# Power_Supply.net
KiCad netlist of a schematic drawn in Altium Designer
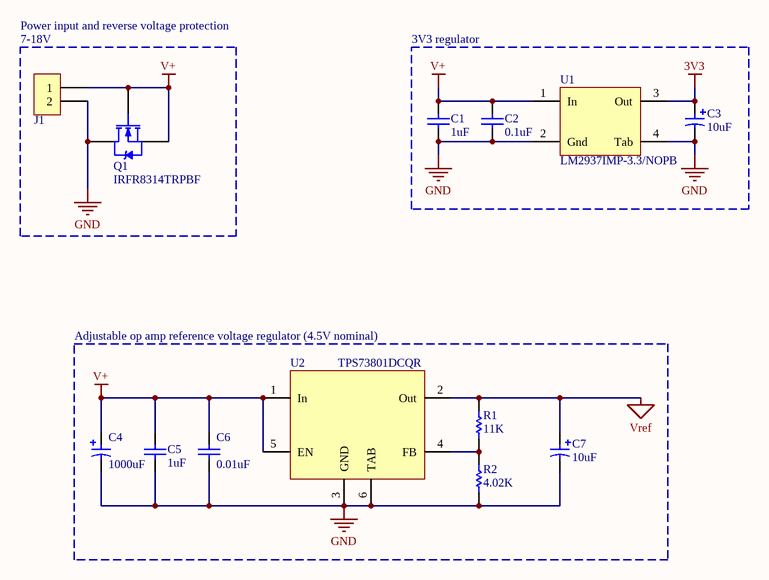
[diagram p0: Power_Supply.SchDoc]

(export (version "E")
  (design (tool "Eeschema 10.0.6"))
  (components
    (comp (ref "C1")
      (value "1uF")
      (footprint "CAPC1608X09N")
      (fields
        (field (name "DIGIKEY PART NUMBER") "490-10487-1-ND")
        (field (name "VOLTAGE") "35V")
        (field (name "MANUFACTURER") "Murata")
      )
      (libsource (lib "Speaker Library") (part "CAP CER 1uF 0603"))
    )
    (comp (ref "C2")
      (value "0.1uF")
      (footprint "CAPC1608X09N")
      (fields
        (field (name "DIGIKEY PART NUMBER") "490-1519-1-ND")
        (field (name "VOLTAGE") "50V")
        (field (name "TOLERANCE") "10%")
      )
      (libsource (lib "Speaker Library") (part "CAP CER 0.1uF 0603"))
    )
    (comp (ref "C3")
      (value "10uF")
      (footprint "CAPMP3216X18N")
      (fields
        (field (name "DIGIKEY PART NUMBER") "399-8431-1-ND")
        (field (name "VOLTAGE") "10V")
        (field (name "TOLERANCE") "10%")
      )
      (libsource (lib "Speaker Library") (part "CAP TANT 10uF 1.8 OHM 10V 1206"))
    )
    (comp (ref "C4")
      (value "1000uF")
      (footprint "Nichicon UVZ 5mm")
      (description "Input Bulk Cap")
      (fields (field (name "DIGIKEY PART NUMBER") "493-1305-ND") (field (name "MANUFACTURER") "Nichicon"))
      (libsource (lib "Speaker Library") (part "CAP ALUM 1000uF SMD"))
    )
    (comp (ref "C5")
      (value "1uF")
      (footprint "CAPC1608X09N")
      (fields
        (field (name "DIGIKEY PART NUMBER") "490-10487-1-ND")
        (field (name "VOLTAGE") "35V")
        (field (name "MANUFACTURER") "Murata")
      )
      (libsource (lib "Speaker Library") (part "CAP CER 1uF 0603"))
    )
    (comp (ref "C6")
      (value "0.01uF")
      (footprint "CAPC1608X09N")
      (fields (field (name "DIGIKEY PART NUMBER") "490-9666-1-ND") (field (name "MANUFACTURER") "Murata"))
      (libsource (lib "Speaker Library") (part "CAP CER 0.01uF 0603"))
    )
    (comp (ref "C7")
      (value "10uF")
      (footprint "CAPMP3216X18N")
      (fields
        (field (name "DIGIKEY PART NUMBER") "399-8431-1-ND")
        (field (name "VOLTAGE") "10V")
        (field (name "TOLERANCE") "10%")
      )
      (libsource (lib "Speaker Library") (part "CAP TANT 10uF 1.8 OHM 10V 1206"))
    )
    (comp (ref "J1")
      (value "TERMINAL BLOCK 2POS")
      (footprint "TERMINAL BLOCK 5MM 2POS")
      (fields (field (name "DIGIKEY PART NUMBER") "ED2561-ND"))
      (libsource (lib "Speaker Library") (part "TERMINAL BLOCK 2POS"))
    )
    (comp (ref "Q1")
      (value "IRFR8314TRPBF")
      (footprint "DPAK229P991X239-3N")
      (description "Reverse Voltage Power MOSFET")
      (fields
        (field (name "DIGIKEY PART NUMBER") "IRFR8314TRPBFCT-ND")
        (field (name "MANUFACTURER") "Infineon Technologies")
      )
      (libsource (lib "Speaker Library") (part "MOSFET_N_CH_30V_179A_D2PAK"))
    )
    (comp (ref "R1")
      (value "11K")
      (footprint "RESC1608X06N")
      (fields
        (field (name "TOLERANCE") "1%")
        (field (name "POWER") "0.1W")
        (field (name "MANUFACTURER") "Yageo")
      )
      (libsource (lib "Speaker Library") (part "RES 11K 0603"))
    )
    (comp (ref "R2")
      (value "4.02K")
      (footprint "RESC1608X06N")
      (fields (field (name "TOLERANCE") "1%") (field (name "DIGIKEY PART NUMBER") "311-4.02KHRCT-ND"))
      (libsource (lib "Speaker Library") (part "RES 4.02K 0603"))
    )
    (comp (ref "U1")
      (value "LM2937IMP-3.3/NOPB")
      (footprint "SOT230P700X180-4N (DCY)")
      (fields (field (name "DIGIKEY PART NUMBER") "LM2937IMP-3.3/NOPBCT-ND"))
      (libsource (lib "Speaker Library") (part "LM2937IMP-3.3/NOPB"))
    )
    (comp (ref "U2")
      (value "TPS73801DCQR")
      (footprint "SOT127P705X180-6M (DCQ)")
      (description "Adjustable 1.21V-20V 1A Regulator")
      (fields (field (name "DIGIKEY PART NUMBER") "296-39489-1-ND"))
      (libsource (lib "Speaker Library") (part "TPS73801DCQR"))
    )
  )
  (nets
    (net (code "1") (name "3V3") (class "Default")
      (node (ref "C3") (pin "1") (pinfunction "1_1") (pintype "passive"))
      (node (ref "U1") (pin "3") (pinfunction "Out_3") (pintype "power_in"))
    )
    (net (code "2") (name "GND") (class "Default")
      (node (ref "C1") (pin "2") (pinfunction "2_2") (pintype "passive"))
      (node (ref "C2") (pin "1") (pinfunction "1_1") (pintype "passive"))
      (node (ref "C3") (pin "2") (pinfunction "2_2") (pintype "passive"))
      (node (ref "C4") (pin "2") (pinfunction "2_2") (pintype "passive"))
      (node (ref "C5") (pin "2") (pinfunction "2_2") (pintype "passive"))
      (node (ref "C6") (pin "1") (pinfunction "1_1") (pintype "passive"))
      (node (ref "C7") (pin "2") (pinfunction "2_2") (pintype "passive"))
      (node (ref "J1") (pin "2") (pinfunction "2_2") (pintype "passive"))
      (node (ref "Q1") (pin "4") (pinfunction "D_4") (pintype "passive"))
      (node (ref "R2") (pin "1") (pinfunction "1_1") (pintype "passive"))
      (node (ref "U1") (pin "2") (pinfunction "Gnd_2") (pintype "power_in"))
      (node (ref "U1") (pin "4") (pinfunction "Tab_4") (pintype "power_in"))
      (node (ref "U2") (pin "3") (pinfunction "GND_3") (pintype "power_in"))
      (node (ref "U2") (pin "6") (pinfunction "TAB_6") (pintype "power_in"))
    )
    (net (code "3") (name "Net-(U2-FB)") (class "Default")
      (node (ref "R1") (pin "1") (pinfunction "1_1") (pintype "passive"))
      (node (ref "R2") (pin "2") (pinfunction "2_2") (pintype "passive"))
      (node (ref "U2") (pin "4") (pinfunction "FB_4") (pintype "power_in"))
    )
    (net (code "4") (name "V+") (class "Default")
      (node (ref "C1") (pin "1") (pinfunction "1_1") (pintype "passive"))
      (node (ref "C2") (pin "2") (pinfunction "2_2") (pintype "passive"))
      (node (ref "C4") (pin "1") (pinfunction "1_1") (pintype "passive"))
      (node (ref "C5") (pin "1") (pinfunction "1_1") (pintype "passive"))
      (node (ref "C6") (pin "2") (pinfunction "2_2") (pintype "passive"))
      (node (ref "J1") (pin "1") (pinfunction "1_1") (pintype "passive"))
      (node (ref "Q1") (pin "1") (pinfunction "G_1") (pintype "passive"))
      (node (ref "Q1") (pin "3") (pinfunction "S_3") (pintype "passive"))
      (node (ref "U1") (pin "1") (pinfunction "In_1") (pintype "power_in"))
      (node (ref "U2") (pin "1") (pinfunction "In_1") (pintype "power_in"))
      (node (ref "U2") (pin "5") (pinfunction "EN_5") (pintype "passive"))
    )
    (net (code "5") (name "Vref") (class "Default")
      (node (ref "C7") (pin "1") (pinfunction "1_1") (pintype "passive"))
      (node (ref "R1") (pin "2") (pinfunction "2_2") (pintype "passive"))
      (node (ref "U2") (pin "2") (pinfunction "Out_2") (pintype "power_in"))
    )
  )
)
